# HW2.net
KiCad netlist of a schematic drawn in EAGLE
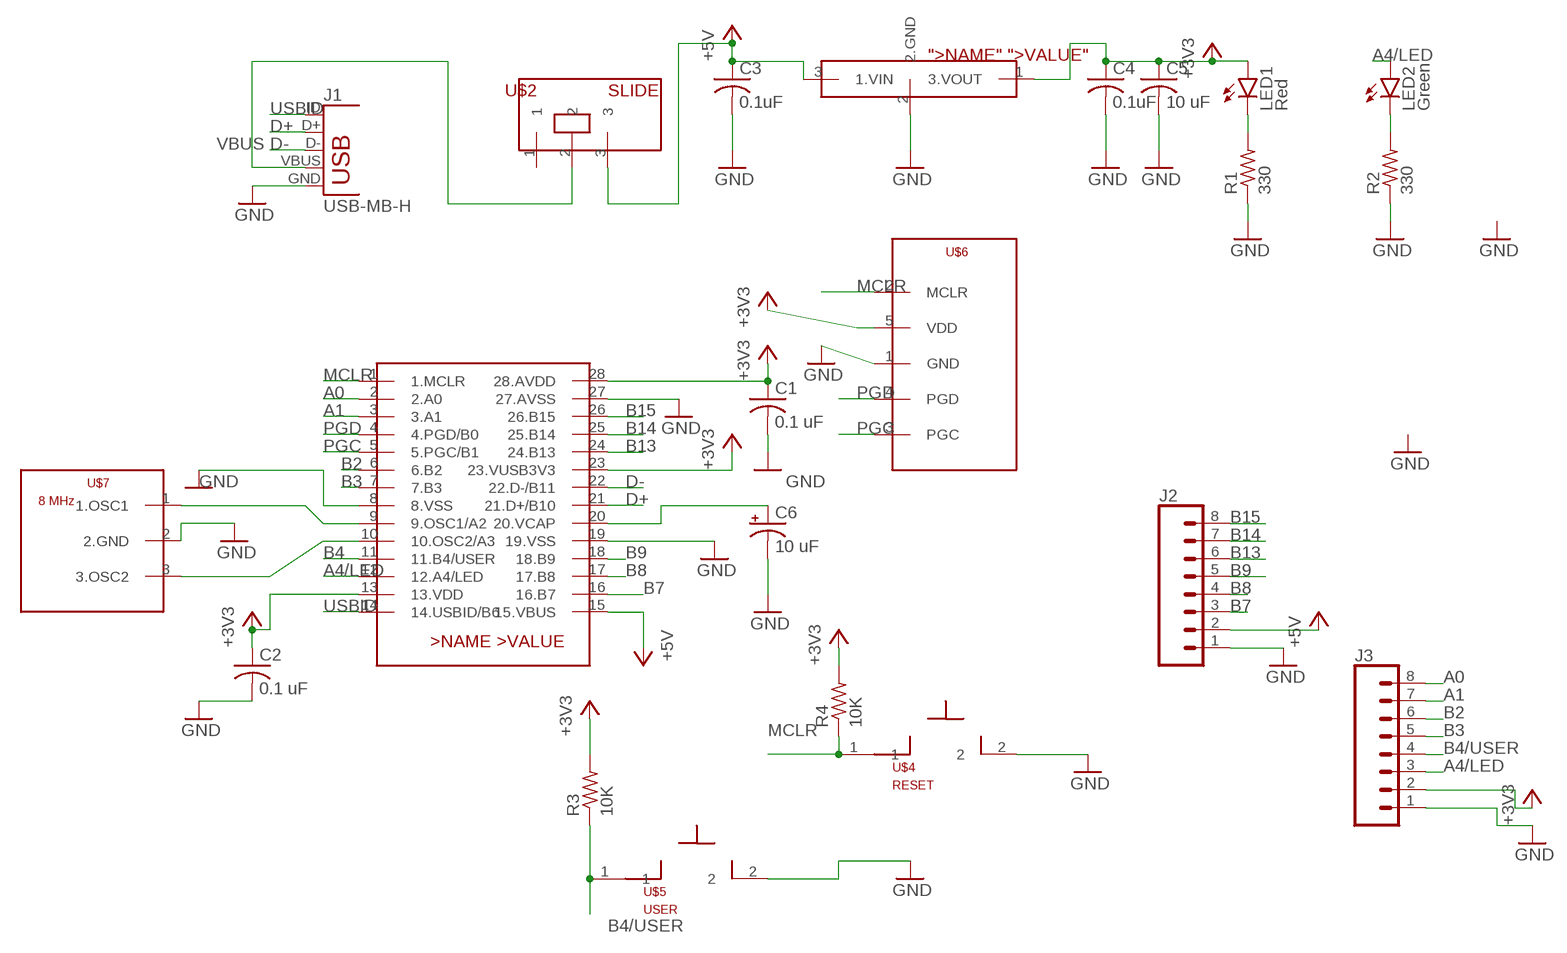
[diagram p0: schematic, sheet 1]

(export (version "E")
  (design (tool "Eeschema 10.0.6"))
  (components
    (comp (ref "C1")
      (value "0.1 uF")
      (footprint "eagle-import:C025-025X050")
      (libsource (lib "eagle-import") (part "C-US025-025X050"))
    )
    (comp (ref "C2")
      (value "0.1 uF")
      (footprint "eagle-import:C025-025X050")
      (libsource (lib "eagle-import") (part "C-US025-025X050"))
    )
    (comp (ref "C3")
      (value "0.1uF")
      (footprint "eagle-import:C025-025X050")
      (libsource (lib "eagle-import") (part "C-US025-025X050"))
    )
    (comp (ref "C4")
      (value "0.1uF")
      (footprint "eagle-import:C025-025X050")
      (libsource (lib "eagle-import") (part "C-US025-025X050"))
    )
    (comp (ref "C5")
      (value "10 uF")
      (footprint "eagle-import:C025-025X050")
      (libsource (lib "eagle-import") (part "C-US025-025X050"))
    )
    (comp (ref "C6")
      (value "10 uF")
      (footprint "eagle-import:B45181B")
      (libsource (lib "eagle-import") (part "CPOL-USB45181B"))
    )
    (comp (ref "J1")
      (value "USB-MB-H")
      (footprint "eagle-import:USB-MB-H")
      (libsource (lib "eagle-import") (part "USB-MB-H"))
    )
    (comp (ref "J2")
      (value "CONN_08\"")
      (footprint "eagle-import:1X08")
      (libsource (lib "eagle-import") (part "CONN_08{dblquote}"))
    )
    (comp (ref "J3")
      (value "CONN_08\"")
      (footprint "eagle-import:1X08")
      (libsource (lib "eagle-import") (part "CONN_08{dblquote}"))
    )
    (comp (ref "LED1")
      (value "Red")
      (footprint "eagle-import:LED3MM")
      (libsource (lib "eagle-import") (part "LED3MM"))
    )
    (comp (ref "LED2")
      (value "Green")
      (footprint "eagle-import:LED3MM")
      (libsource (lib "eagle-import") (part "LED3MM"))
    )
    (comp (ref "R1")
      (value "330")
      (footprint "eagle-import:0207_10")
      (libsource (lib "eagle-import") (part "R-US_0207/10"))
    )
    (comp (ref "R2")
      (value "330")
      (footprint "eagle-import:0207_10")
      (libsource (lib "eagle-import") (part "R-US_0207/10"))
    )
    (comp (ref "R3")
      (value "10K")
      (footprint "eagle-import:0207_10")
      (libsource (lib "eagle-import") (part "R-US_0207/10"))
    )
    (comp (ref "R4")
      (value "10K")
      (footprint "eagle-import:0207_10")
      (libsource (lib "eagle-import") (part "R-US_0207/10"))
    )
    (comp (ref "U$1")
      (value "PIC32MX270F256D")
      (footprint "eagle-import:DIL28-3")
      (libsource (lib "eagle-import") (part "PIC32MX270F256D"))
    )
    (comp (ref "U$2")
      (value "SLIDE")
      (footprint "eagle-import:SLIDE")
      (libsource (lib "eagle-import") (part "SLIDE"))
    )
    (comp (ref "U$3")
      (value "L4931")
      (footprint "eagle-import:TO92")
      (libsource (lib "eagle-import") (part "L4931"))
    )
    (comp (ref "U$4")
      (value "RESET")
      (footprint "eagle-import:PB")
      (libsource (lib "eagle-import") (part "PB"))
    )
    (comp (ref "U$5")
      (value "USER")
      (footprint "eagle-import:PB")
      (libsource (lib "eagle-import") (part "PB"))
    )
    (comp (ref "U$6")
      (value "PICKIT3")
      (footprint "eagle-import:1X05")
      (libsource (lib "eagle-import") (part "PICKIT3"))
    )
    (comp (ref "U$7")
      (value "8 MHz")
      (footprint "eagle-import:OSC")
      (libsource (lib "eagle-import") (part "OSC"))
    )
  )
  (nets
    (net (code "1") (name "+3V3") (class "Default")
      (node (ref "C1") (pin "1") (pinfunction "1_1") (pintype "passive"))
      (node (ref "C2") (pin "1") (pinfunction "1_1") (pintype "passive"))
      (node (ref "C4") (pin "1") (pinfunction "1_1") (pintype "passive"))
      (node (ref "C5") (pin "1") (pinfunction "1_1") (pintype "passive"))
      (node (ref "J3") (pin "2") (pinfunction "2_2") (pintype "passive"))
      (node (ref "LED1") (pin "A") (pinfunction "A_A") (pintype "passive"))
      (node (ref "R3") (pin "2") (pinfunction "2_2") (pintype "passive"))
      (node (ref "R4") (pin "2") (pinfunction "2_2") (pintype "passive"))
      (node (ref "U$1") (pin "13") (pinfunction "13.VDD_13") (pintype "bidirectional"))
      (node (ref "U$1") (pin "23") (pinfunction "23.VUSB3V3_23") (pintype "bidirectional"))
      (node (ref "U$1") (pin "28") (pinfunction "28.AVDD_28") (pintype "bidirectional"))
      (node (ref "U$3") (pin "1") (pinfunction "3.VOUT_1") (pintype "bidirectional"))
      (node (ref "U$6") (pin "5") (pinfunction "VDD_5") (pintype "bidirectional"))
    )
    (net (code "2") (name "+5V") (class "Default")
      (node (ref "C3") (pin "1") (pinfunction "1_1") (pintype "passive"))
      (node (ref "J2") (pin "2") (pinfunction "2_2") (pintype "passive"))
      (node (ref "U$1") (pin "15") (pinfunction "15.VBUS_15") (pintype "bidirectional"))
      (node (ref "U$2") (pin "3") (pinfunction "3_3") (pintype "bidirectional"))
      (node (ref "U$3") (pin "3") (pinfunction "1.VIN_3") (pintype "bidirectional"))
    )
    (net (code "3") (name "/A0") (class "Default")
      (node (ref "J3") (pin "8") (pinfunction "8_8") (pintype "passive"))
      (node (ref "U$1") (pin "2") (pinfunction "2.A0_2") (pintype "bidirectional"))
    )
    (net (code "4") (name "/A1") (class "Default")
      (node (ref "J3") (pin "7") (pinfunction "7_7") (pintype "passive"))
      (node (ref "U$1") (pin "3") (pinfunction "3.A1_3") (pintype "bidirectional"))
    )
    (net (code "5") (name "/A4{slash}LED") (class "Default")
      (node (ref "J3") (pin "3") (pinfunction "3_3") (pintype "passive"))
      (node (ref "LED2") (pin "A") (pinfunction "A_A") (pintype "passive"))
      (node (ref "U$1") (pin "12") (pinfunction "12.A4/LED_12") (pintype "bidirectional"))
    )
    (net (code "6") (name "/B2") (class "Default")
      (node (ref "J3") (pin "6") (pinfunction "6_6") (pintype "passive"))
      (node (ref "U$1") (pin "6") (pinfunction "6.B2_6") (pintype "bidirectional"))
    )
    (net (code "7") (name "/B3") (class "Default")
      (node (ref "J3") (pin "5") (pinfunction "5_5") (pintype "passive"))
      (node (ref "U$1") (pin "7") (pinfunction "7.B3_7") (pintype "bidirectional"))
    )
    (net (code "8") (name "/B4") (class "Default")
      (node (ref "U$1") (pin "11") (pinfunction "11.B4/USER_11") (pintype "bidirectional"))
    )
    (net (code "9") (name "/B4{slash}USER") (class "Default")
      (node (ref "J3") (pin "4") (pinfunction "4_4") (pintype "passive"))
      (node (ref "R3") (pin "1") (pinfunction "1_1") (pintype "passive"))
      (node (ref "U$5") (pin "1") (pinfunction "1_1") (pintype "bidirectional"))
    )
    (net (code "10") (name "/B7") (class "Default")
      (node (ref "J2") (pin "3") (pinfunction "3_3") (pintype "passive"))
      (node (ref "U$1") (pin "16") (pinfunction "16.B7_16") (pintype "bidirectional"))
    )
    (net (code "11") (name "/B8") (class "Default")
      (node (ref "J2") (pin "4") (pinfunction "4_4") (pintype "passive"))
      (node (ref "U$1") (pin "17") (pinfunction "17.B8_17") (pintype "bidirectional"))
    )
    (net (code "12") (name "/B9") (class "Default")
      (node (ref "J2") (pin "5") (pinfunction "5_5") (pintype "passive"))
      (node (ref "U$1") (pin "18") (pinfunction "18.B9_18") (pintype "bidirectional"))
    )
    (net (code "13") (name "/B13") (class "Default")
      (node (ref "J2") (pin "6") (pinfunction "6_6") (pintype "passive"))
      (node (ref "U$1") (pin "24") (pinfunction "24.B13_24") (pintype "bidirectional"))
    )
    (net (code "14") (name "/B14") (class "Default")
      (node (ref "J2") (pin "7") (pinfunction "7_7") (pintype "passive"))
      (node (ref "U$1") (pin "25") (pinfunction "25.B14_25") (pintype "bidirectional"))
    )
    (net (code "15") (name "/B15") (class "Default")
      (node (ref "J2") (pin "8") (pinfunction "8_8") (pintype "passive"))
      (node (ref "U$1") (pin "26") (pinfunction "26.B15_26") (pintype "bidirectional"))
    )
    (net (code "16") (name "/D+") (class "Default")
      (node (ref "J1") (pin "D+") (pinfunction "D+_D+") (pintype "bidirectional"))
      (node (ref "U$1") (pin "21") (pinfunction "21.D+/B10_21") (pintype "bidirectional"))
    )
    (net (code "17") (name "/D-") (class "Default")
      (node (ref "J1") (pin "D-") (pinfunction "D-_D-") (pintype "bidirectional"))
      (node (ref "U$1") (pin "22") (pinfunction "22.D-/B11_22") (pintype "bidirectional"))
    )
    (net (code "18") (name "/MCLR") (class "Default")
      (node (ref "R4") (pin "1") (pinfunction "1_1") (pintype "passive"))
      (node (ref "U$1") (pin "1") (pinfunction "1.MCLR_1") (pintype "bidirectional"))
      (node (ref "U$4") (pin "1") (pinfunction "1_1") (pintype "bidirectional"))
      (node (ref "U$6") (pin "2") (pinfunction "MCLR_2") (pintype "bidirectional"))
    )
    (net (code "19") (name "/PGC") (class "Default")
      (node (ref "U$1") (pin "5") (pinfunction "5.PGC/B1_5") (pintype "bidirectional"))
      (node (ref "U$6") (pin "3") (pinfunction "PGC_3") (pintype "bidirectional"))
    )
    (net (code "20") (name "/PGD") (class "Default")
      (node (ref "U$1") (pin "4") (pinfunction "4.PGD/B0_4") (pintype "bidirectional"))
      (node (ref "U$6") (pin "4") (pinfunction "PGD_4") (pintype "bidirectional"))
    )
    (net (code "21") (name "/USBID") (class "Default")
      (node (ref "J1") (pin "ID") (pinfunction "ID_ID") (pintype "bidirectional"))
      (node (ref "U$1") (pin "14") (pinfunction "14.USBID/B6_14") (pintype "bidirectional"))
    )
    (net (code "22") (name "/VBUS") (class "Default")
      (node (ref "J1") (pin "VBUS") (pinfunction "VBUS_VBUS") (pintype "bidirectional"))
      (node (ref "U$2") (pin "2") (pinfunction "2_2") (pintype "bidirectional"))
    )
    (net (code "23") (name "GND") (class "Default")
      (node (ref "C1") (pin "2") (pinfunction "2_2") (pintype "passive"))
      (node (ref "C2") (pin "2") (pinfunction "2_2") (pintype "passive"))
      (node (ref "C3") (pin "2") (pinfunction "2_2") (pintype "passive"))
      (node (ref "C4") (pin "2") (pinfunction "2_2") (pintype "passive"))
      (node (ref "C5") (pin "2") (pinfunction "2_2") (pintype "passive"))
      (node (ref "C6") (pin "-") (pinfunction "-_-") (pintype "passive"))
      (node (ref "J1") (pin "GND") (pinfunction "GND_GND") (pintype "bidirectional"))
      (node (ref "J2") (pin "1") (pinfunction "1_1") (pintype "passive"))
      (node (ref "J3") (pin "1") (pinfunction "1_1") (pintype "passive"))
      (node (ref "R1") (pin "1") (pinfunction "1_1") (pintype "passive"))
      (node (ref "R2") (pin "1") (pinfunction "1_1") (pintype "passive"))
      (node (ref "U$1") (pin "19") (pinfunction "19.VSS_19") (pintype "bidirectional"))
      (node (ref "U$1") (pin "27") (pinfunction "27.AVSS_27") (pintype "bidirectional"))
      (node (ref "U$1") (pin "8") (pinfunction "8.VSS_8") (pintype "bidirectional"))
      (node (ref "U$3") (pin "2") (pinfunction "2.GND_2") (pintype "bidirectional"))
      (node (ref "U$4") (pin "2") (pinfunction "2_2") (pintype "bidirectional"))
      (node (ref "U$5") (pin "2") (pinfunction "2_2") (pintype "bidirectional"))
      (node (ref "U$6") (pin "1") (pinfunction "GND_1") (pintype "bidirectional"))
      (node (ref "U$7") (pin "2") (pinfunction "2.GND_2") (pintype "bidirectional"))
    )
    (net (code "24") (name "Net-(LED1-C)") (class "Default")
      (node (ref "LED1") (pin "K") (pinfunction "C_K") (pintype "passive"))
      (node (ref "R1") (pin "2") (pinfunction "2_2") (pintype "passive"))
    )
    (net (code "25") (name "Net-(LED2-C)") (class "Default")
      (node (ref "LED2") (pin "K") (pinfunction "C_K") (pintype "passive"))
      (node (ref "R2") (pin "2") (pinfunction "2_2") (pintype "passive"))
    )
    (net (code "26") (name "Net-(U$1-9.OSC1{slash}A2)") (class "Default")
      (node (ref "U$1") (pin "9") (pinfunction "9.OSC1/A2_9") (pintype "bidirectional"))
      (node (ref "U$7") (pin "1") (pinfunction "1.OSC1_1") (pintype "bidirectional"))
    )
    (net (code "27") (name "Net-(U$1-10.OSC2{slash}A3)") (class "Default")
      (node (ref "U$1") (pin "10") (pinfunction "10.OSC2/A3_10") (pintype "bidirectional"))
      (node (ref "U$7") (pin "3") (pinfunction "3.OSC2_3") (pintype "bidirectional"))
    )
    (net (code "28") (name "Net-(U$1-20.VCAP)") (class "Default")
      (node (ref "C6") (pin "+") (pinfunction "+_+") (pintype "passive"))
      (node (ref "U$1") (pin "20") (pinfunction "20.VCAP_20") (pintype "bidirectional"))
    )
    (net (code "29") (name "unconnected-(U$2-Pad1)") (class "Default")
      (node (ref "U$2") (pin "1") (pinfunction "1_1") (pintype "bidirectional"))
    )
  )
)
